# UNO-TH_Rev3e.net
KiCad netlist of a schematic drawn in EAGLE
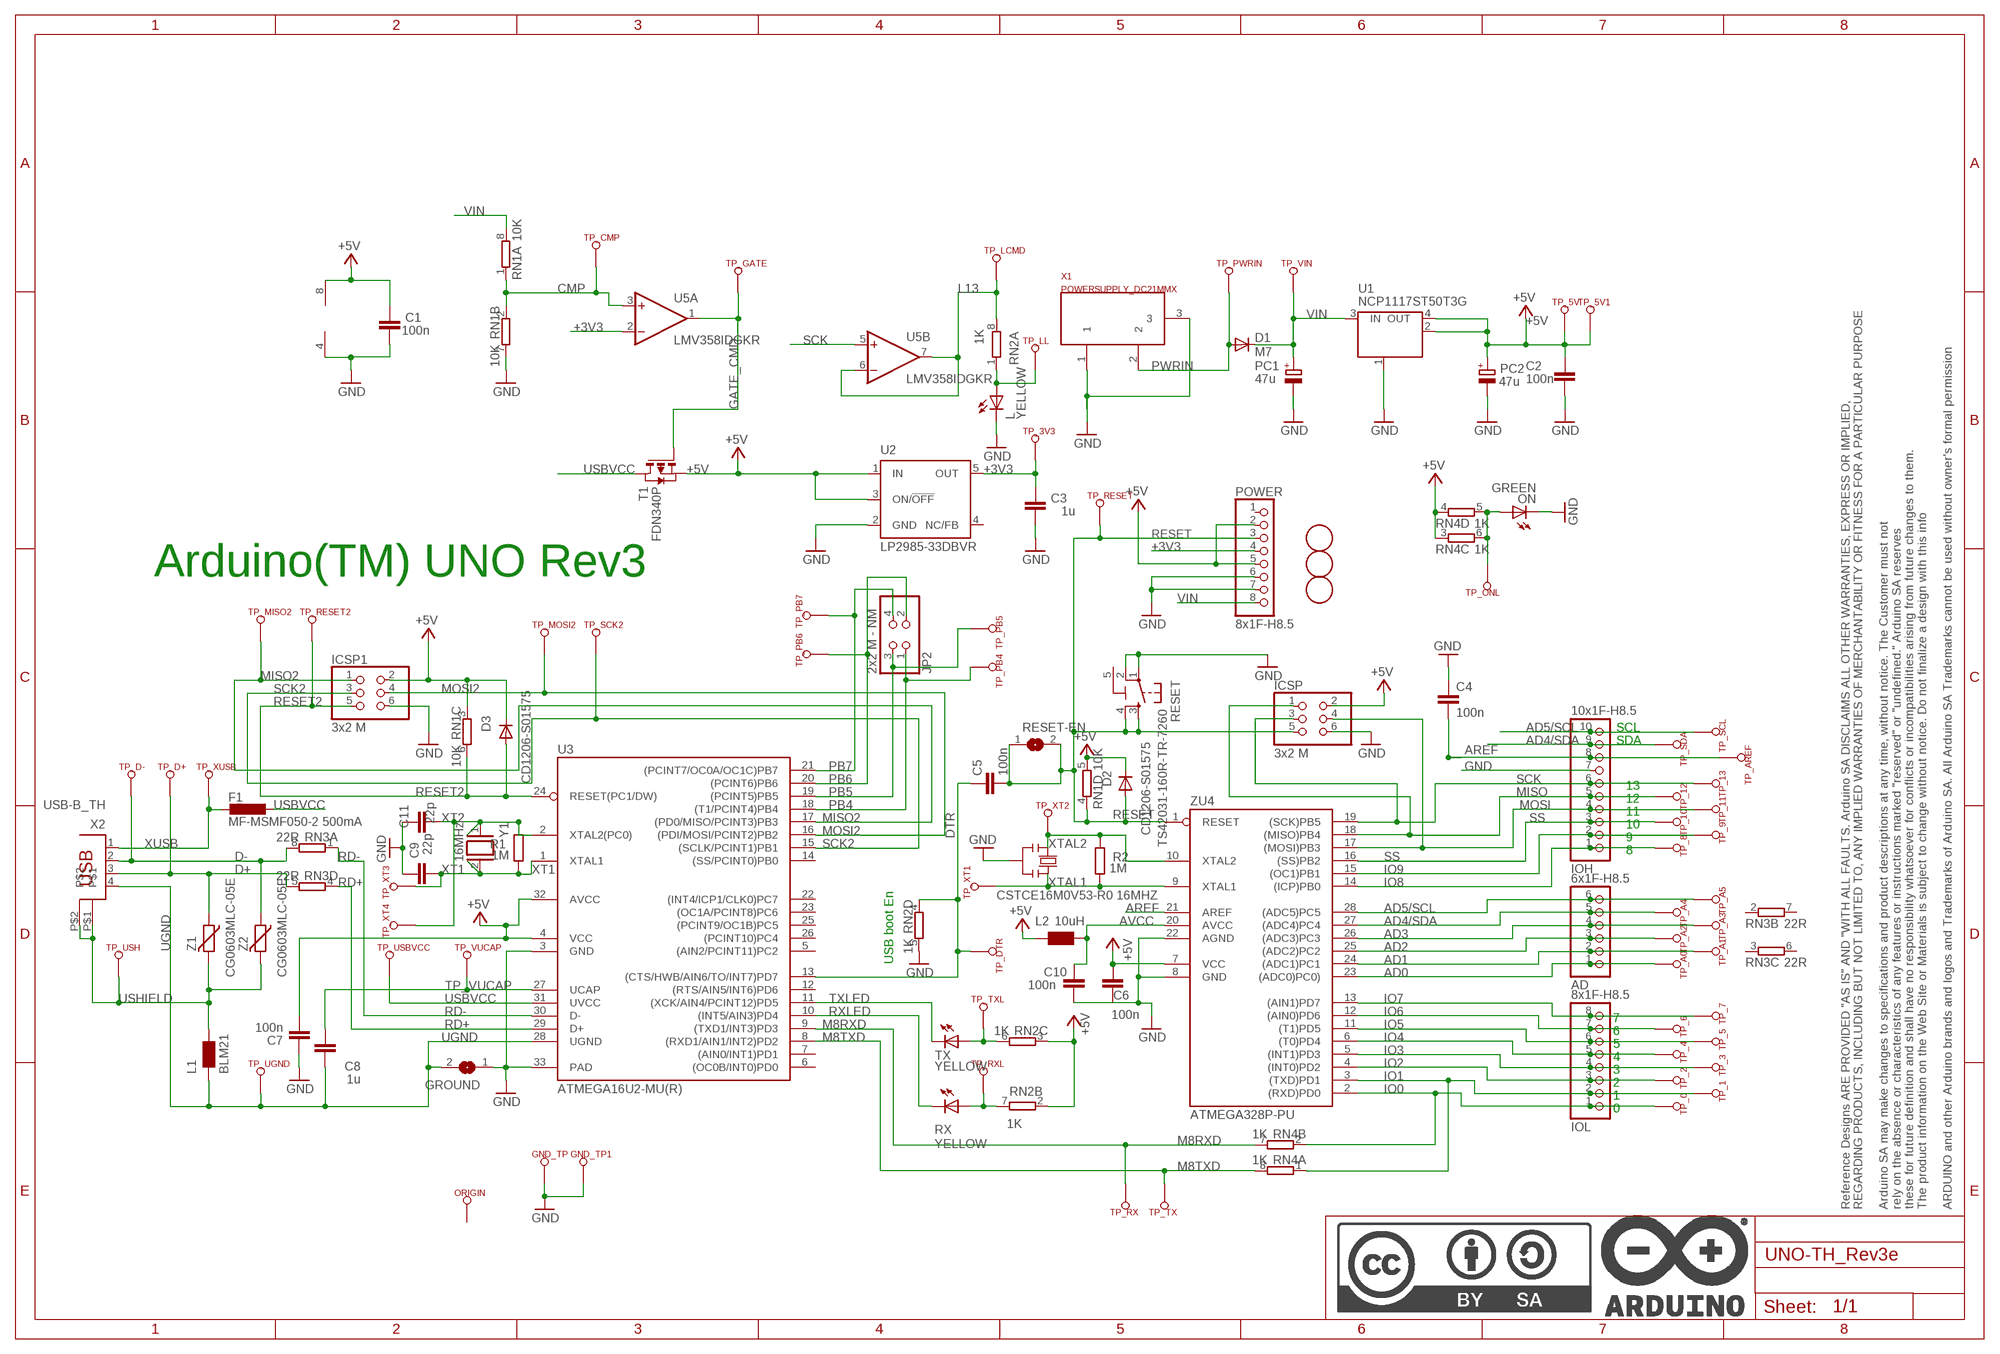
[diagram p0: schematic, sheet 1]

(export (version "E")
  (design (tool "Eeschema 10.0.6"))
  (components
    (comp (ref "AD")
      (value "6x1F-H8.5")
      (footprint "eagle-import:1X06")
      (libsource (lib "eagle-import") (part "PINHD-1X6"))
    )
    (comp (ref "C1")
      (value "100n")
      (footprint "eagle-import:C0603-ROUND")
      (libsource (lib "eagle-import") (part "C-EU0603-RND"))
    )
    (comp (ref "C2")
      (value "100n")
      (footprint "eagle-import:C0603-ROUND")
      (libsource (lib "eagle-import") (part "C-EU0603-RND"))
    )
    (comp (ref "C3")
      (value "1u")
      (footprint "eagle-import:C0603-ROUND")
      (libsource (lib "eagle-import") (part "C-EU0603-RND"))
    )
    (comp (ref "C4")
      (value "100n")
      (footprint "eagle-import:C0603-ROUND")
      (libsource (lib "eagle-import") (part "C-EU0603-RND"))
    )
    (comp (ref "C5")
      (value "100n")
      (footprint "eagle-import:C0603-ROUND")
      (libsource (lib "eagle-import") (part "C-EU0603-RND"))
    )
    (comp (ref "C6")
      (value "100n")
      (footprint "eagle-import:C0603-ROUND")
      (libsource (lib "eagle-import") (part "C-EU0603-RND"))
    )
    (comp (ref "C7")
      (value "100n")
      (footprint "eagle-import:C0603-ROUND")
      (libsource (lib "eagle-import") (part "C-EU0603-RND"))
    )
    (comp (ref "C8")
      (value "1u")
      (footprint "eagle-import:C0603-ROUND")
      (libsource (lib "eagle-import") (part "C-EU0603-RND"))
    )
    (comp (ref "C9")
      (value "22p")
      (footprint "eagle-import:C0603-ROUND")
      (libsource (lib "eagle-import") (part "C-EU0603-RND"))
    )
    (comp (ref "C10")
      (value "100n")
      (footprint "eagle-import:C0603-ROUND")
      (libsource (lib "eagle-import") (part "C-EU0603-RND"))
    )
    (comp (ref "C11")
      (value "22p")
      (footprint "eagle-import:C0603-ROUND")
      (libsource (lib "eagle-import") (part "C-EU0603-RND"))
    )
    (comp (ref "D1")
      (value "M7")
      (footprint "eagle-import:SMB")
      (libsource (lib "eagle-import") (part "DIODE-SMB"))
    )
    (comp (ref "D2")
      (value "CD1206-S01575")
      (footprint "eagle-import:MINIMELF")
      (libsource (lib "eagle-import") (part "DIODE-MINIMELF"))
    )
    (comp (ref "D3")
      (value "CD1206-S01575")
      (footprint "eagle-import:MINIMELF")
      (libsource (lib "eagle-import") (part "DIODE-MINIMELF"))
    )
    (comp (ref "F1")
      (value "MF-MSMF050-2 500mA")
      (footprint "eagle-import:L1812")
      (libsource (lib "eagle-import") (part "L-EUL1812"))
    )
    (comp (ref "FD1")
      (value "FIDUCIALMOUNT")
      (footprint "eagle-import:FIDUCIA-MOUNT")
      (libsource (lib "eagle-import") (part "FIDUCIALMOUNT"))
    )
    (comp (ref "FD2")
      (value "FIDUCIALMOUNT")
      (footprint "eagle-import:FIDUCIA-MOUNT")
      (libsource (lib "eagle-import") (part "FIDUCIALMOUNT"))
    )
    (comp (ref "FD3")
      (value "FIDUCIALMOUNT")
      (footprint "eagle-import:FIDUCIA-MOUNT")
      (libsource (lib "eagle-import") (part "FIDUCIALMOUNT"))
    )
    (comp (ref "FRAME1")
      (value "DNP")
      (footprint "eagle-import:FRAME")
      (libsource (lib "eagle-import") (part "A3-FRAME"))
    )
    (comp (ref "GND_TP")
      (value "TP_SP")
      (footprint "eagle-import:TP-SP")
      (libsource (lib "eagle-import") (part "TP_SP"))
    )
    (comp (ref "GND_TP1")
      (value "TP_SP")
      (footprint "eagle-import:TP-SP")
      (libsource (lib "eagle-import") (part "TP_SP"))
    )
    (comp (ref "GROUND")
      (value "SJ")
      (footprint "eagle-import:SJ")
      (libsource (lib "eagle-import") (part "SJ"))
    )
    (comp (ref "ICSP")
      (value "3x2 M")
      (footprint "eagle-import:2X03")
      (libsource (lib "eagle-import") (part "PINHD-2X3"))
    )
    (comp (ref "ICSP1")
      (value "3x2 M")
      (footprint "eagle-import:2X03")
      (libsource (lib "eagle-import") (part "PINHD-2X3"))
    )
    (comp (ref "IOH")
      (value "10x1F-H8.5")
      (footprint "eagle-import:1X10")
      (libsource (lib "eagle-import") (part "PINHD-1X10_ARD"))
    )
    (comp (ref "IOL")
      (value "8x1F-H8.5")
      (footprint "eagle-import:1X08")
      (libsource (lib "eagle-import") (part "PINHD-1X8"))
    )
    (comp (ref "JP2")
      (value "2x2 M - NM")
      (footprint "eagle-import:2X02")
      (libsource (lib "eagle-import") (part "PINHD-2X2"))
    )
    (comp (ref "L")
      (value "YELLOW")
      (footprint "eagle-import:CHIP-LED0805")
      (libsource (lib "eagle-import") (part "LEDCHIP-LED0805"))
    )
    (comp (ref "L1")
      (value "BLM21")
      (footprint "eagle-import:0805")
      (libsource (lib "eagle-import") (part "WE-CBF_0805"))
    )
    (comp (ref "L2")
      (value "10uH")
      (footprint "eagle-import:0805")
      (fields (field (name "PART_NUMBER") "CV201210-100K"))
      (libsource (lib "eagle-import") (part "0715_CV201210-100K"))
    )
    (comp (ref "ON")
      (value "GREEN")
      (footprint "eagle-import:CHIP-LED0805")
      (libsource (lib "eagle-import") (part "LEDCHIP-LED0805"))
    )
    (comp (ref "ORIGIN")
      (value "TP_SP")
      (footprint "eagle-import:TP-SP")
      (libsource (lib "eagle-import") (part "TP_SP"))
    )
    (comp (ref "PC1")
      (value "47u")
      (footprint "eagle-import:PANASONIC_D")
      (libsource (lib "eagle-import") (part "CPOL-EUD"))
    )
    (comp (ref "PC2")
      (value "47u")
      (footprint "eagle-import:PANASONIC_D")
      (libsource (lib "eagle-import") (part "CPOL-EUD"))
    )
    (comp (ref "POWER")
      (value "8x1F-H8.5")
      (footprint "eagle-import:1X08")
      (libsource (lib "eagle-import") (part "PINHD-1X8"))
    )
    (comp (ref "R1")
      (value "1M")
      (footprint "eagle-import:R0603-ROUND")
      (libsource (lib "eagle-import") (part "R-EU_R0603"))
    )
    (comp (ref "R2")
      (value "1M")
      (footprint "eagle-import:R0603-ROUND")
      (libsource (lib "eagle-import") (part "R-EU_R0603"))
    )
    (comp (ref "RESET")
      (value "TS42031-160R-TR-7260")
      (footprint "eagle-import:TS42")
      (libsource (lib "eagle-import") (part "TS42"))
    )
    (comp (ref "RESET-EN")
      (value "SJ")
      (footprint "eagle-import:SJ")
      (libsource (lib "eagle-import") (part "SJ"))
    )
    (comp (ref "RN1")
      (value "10K")
      (footprint "eagle-import:CAY16")
      (libsource (lib "eagle-import") (part "4R-NCAY16"))
    )
    (comp (ref "RN2")
      (value "1K")
      (footprint "eagle-import:CAY16")
      (libsource (lib "eagle-import") (part "4R-NCAY16"))
    )
    (comp (ref "RN3")
      (value "22R")
      (footprint "eagle-import:CAY16")
      (libsource (lib "eagle-import") (part "4R-NCAY16"))
    )
    (comp (ref "RN4")
      (value "1K")
      (footprint "eagle-import:CAY16")
      (libsource (lib "eagle-import") (part "4R-NCAY16"))
    )
    (comp (ref "RX")
      (value "YELLOW")
      (footprint "eagle-import:CHIP-LED0805")
      (libsource (lib "eagle-import") (part "LEDCHIP-LED0805"))
    )
    (comp (ref "T1")
      (value "FDN340P")
      (footprint "eagle-import:SOT-23")
      (libsource (lib "eagle-import") (part "PMOSSOT23"))
    )
    (comp (ref "TP_0")
      (value "TP_SP")
      (footprint "eagle-import:TP-SP")
      (libsource (lib "eagle-import") (part "TP_SP"))
    )
    (comp (ref "TP_1")
      (value "TP_SP")
      (footprint "eagle-import:TP-SP")
      (libsource (lib "eagle-import") (part "TP_SP"))
    )
    (comp (ref "TP_2")
      (value "TP_SP")
      (footprint "eagle-import:TP-SP")
      (libsource (lib "eagle-import") (part "TP_SP"))
    )
    (comp (ref "TP_3")
      (value "TP_SP")
      (footprint "eagle-import:TP-SP")
      (libsource (lib "eagle-import") (part "TP_SP"))
    )
    (comp (ref "TP_3V3")
      (value "TP_SP")
      (footprint "eagle-import:TP-SP")
      (libsource (lib "eagle-import") (part "TP_SP"))
    )
    (comp (ref "TP_4")
      (value "TP_SP")
      (footprint "eagle-import:TP-SP")
      (libsource (lib "eagle-import") (part "TP_SP"))
    )
    (comp (ref "TP_5")
      (value "TP_SP")
      (footprint "eagle-import:TP-SP")
      (libsource (lib "eagle-import") (part "TP_SP"))
    )
    (comp (ref "TP_5V")
      (value "TP_SP")
      (footprint "eagle-import:TP-SP")
      (libsource (lib "eagle-import") (part "TP_SP"))
    )
    (comp (ref "TP_5V1")
      (value "TP_SP")
      (footprint "eagle-import:TP-SP")
      (libsource (lib "eagle-import") (part "TP_SP"))
    )
    (comp (ref "TP_6")
      (value "TP_SP")
      (footprint "eagle-import:TP-SP")
      (libsource (lib "eagle-import") (part "TP_SP"))
    )
    (comp (ref "TP_7")
      (value "TP_SP")
      (footprint "eagle-import:TP-SP")
      (libsource (lib "eagle-import") (part "TP_SP"))
    )
    (comp (ref "TP_8")
      (value "TP_SP")
      (footprint "eagle-import:TP-SP")
      (libsource (lib "eagle-import") (part "TP_SP"))
    )
    (comp (ref "TP_9")
      (value "TP_SP")
      (footprint "eagle-import:TP-SP")
      (libsource (lib "eagle-import") (part "TP_SP"))
    )
    (comp (ref "TP_10")
      (value "TP_SP")
      (footprint "eagle-import:TP-SP")
      (libsource (lib "eagle-import") (part "TP_SP"))
    )
    (comp (ref "TP_11")
      (value "TP_SP")
      (footprint "eagle-import:TP-SP")
      (libsource (lib "eagle-import") (part "TP_SP"))
    )
    (comp (ref "TP_12")
      (value "TP_SP")
      (footprint "eagle-import:TP-SP")
      (libsource (lib "eagle-import") (part "TP_SP"))
    )
    (comp (ref "TP_13")
      (value "TP_SP")
      (footprint "eagle-import:TP-SP")
      (libsource (lib "eagle-import") (part "TP_SP"))
    )
    (comp (ref "TP_A0")
      (value "TP_SP")
      (footprint "eagle-import:TP-SP")
      (libsource (lib "eagle-import") (part "TP_SP"))
    )
    (comp (ref "TP_A1")
      (value "TP_SP")
      (footprint "eagle-import:TP-SP")
      (libsource (lib "eagle-import") (part "TP_SP"))
    )
    (comp (ref "TP_A2")
      (value "TP_SP")
      (footprint "eagle-import:TP-SP")
      (libsource (lib "eagle-import") (part "TP_SP"))
    )
    (comp (ref "TP_A3")
      (value "TP_SP")
      (footprint "eagle-import:TP-SP")
      (libsource (lib "eagle-import") (part "TP_SP"))
    )
    (comp (ref "TP_A4")
      (value "TP_SP")
      (footprint "eagle-import:TP-SP")
      (libsource (lib "eagle-import") (part "TP_SP"))
    )
    (comp (ref "TP_A5")
      (value "TP_SP")
      (footprint "eagle-import:TP-SP")
      (libsource (lib "eagle-import") (part "TP_SP"))
    )
    (comp (ref "TP_AREF")
      (value "TP_SP")
      (footprint "eagle-import:TP-SP")
      (libsource (lib "eagle-import") (part "TP_SP"))
    )
    (comp (ref "TP_CMP")
      (value "TP_SP")
      (footprint "eagle-import:TP-SP")
      (libsource (lib "eagle-import") (part "TP_SP"))
    )
    (comp (ref "TP_D+")
      (value "TP_SP")
      (footprint "eagle-import:TP-SP")
      (libsource (lib "eagle-import") (part "TP_SP"))
    )
    (comp (ref "TP_D-")
      (value "TP_SP")
      (footprint "eagle-import:TP-SP")
      (libsource (lib "eagle-import") (part "TP_SP"))
    )
    (comp (ref "TP_DTR")
      (value "TP_SP")
      (footprint "eagle-import:TP-SP")
      (libsource (lib "eagle-import") (part "TP_SP"))
    )
    (comp (ref "TP_GATE")
      (value "TP_SP")
      (footprint "eagle-import:TP-SP")
      (libsource (lib "eagle-import") (part "TP_SP"))
    )
    (comp (ref "TP_LCMD")
      (value "TP_SP")
      (footprint "eagle-import:TP-SP")
      (libsource (lib "eagle-import") (part "TP_SP"))
    )
    (comp (ref "TP_LL")
      (value "TP_SP")
      (footprint "eagle-import:TP-SP")
      (libsource (lib "eagle-import") (part "TP_SP"))
    )
    (comp (ref "TP_MISO2")
      (value "TP_SP")
      (footprint "eagle-import:TP-SP")
      (libsource (lib "eagle-import") (part "TP_SP"))
    )
    (comp (ref "TP_MOSI2")
      (value "TP_SP")
      (footprint "eagle-import:TP-SP")
      (libsource (lib "eagle-import") (part "TP_SP"))
    )
    (comp (ref "TP_ONL")
      (value "TP_SP")
      (footprint "eagle-import:TP-SP")
      (libsource (lib "eagle-import") (part "TP_SP"))
    )
    (comp (ref "TP_PB4")
      (value "TP_SP")
      (footprint "eagle-import:TP-SP")
      (libsource (lib "eagle-import") (part "TP_SP"))
    )
    (comp (ref "TP_PB5")
      (value "TP_SP")
      (footprint "eagle-import:TP-SP")
      (libsource (lib "eagle-import") (part "TP_SP"))
    )
    (comp (ref "TP_PB6")
      (value "TP_SP")
      (footprint "eagle-import:TP-SP")
      (libsource (lib "eagle-import") (part "TP_SP"))
    )
    (comp (ref "TP_PB7")
      (value "TP_SP")
      (footprint "eagle-import:TP-SP")
      (libsource (lib "eagle-import") (part "TP_SP"))
    )
    (comp (ref "TP_PWRIN")
      (value "TP_SP")
      (footprint "eagle-import:TP-SP")
      (libsource (lib "eagle-import") (part "TP_SP"))
    )
    (comp (ref "TP_RESET")
      (value "TP_SP")
      (footprint "eagle-import:TP-SP")
      (libsource (lib "eagle-import") (part "TP_SP"))
    )
    (comp (ref "TP_RESET2")
      (value "TP_SP")
      (footprint "eagle-import:TP-SP")
      (libsource (lib "eagle-import") (part "TP_SP"))
    )
    (comp (ref "TP_RX")
      (value "TP_SP")
      (footprint "eagle-import:TP-SP")
      (libsource (lib "eagle-import") (part "TP_SP"))
    )
    (comp (ref "TP_RXL")
      (value "TP_SP")
      (footprint "eagle-import:TP-SP")
      (libsource (lib "eagle-import") (part "TP_SP"))
    )
    (comp (ref "TP_SCK2")
      (value "TP_SP")
      (footprint "eagle-import:TP-SP")
      (libsource (lib "eagle-import") (part "TP_SP"))
    )
    (comp (ref "TP_SCL")
      (value "TP_SP")
      (footprint "eagle-import:TP-SP")
      (libsource (lib "eagle-import") (part "TP_SP"))
    )
    (comp (ref "TP_SDA")
      (value "TP_SP")
      (footprint "eagle-import:TP-SP")
      (libsource (lib "eagle-import") (part "TP_SP"))
    )
    (comp (ref "TP_TX")
      (value "TP_SP")
      (footprint "eagle-import:TP-SP")
      (libsource (lib "eagle-import") (part "TP_SP"))
    )
    (comp (ref "TP_TXL")
      (value "TP_SP")
      (footprint "eagle-import:TP-SP")
      (libsource (lib "eagle-import") (part "TP_SP"))
    )
    (comp (ref "TP_UGND")
      (value "TP_SP")
      (footprint "eagle-import:TP-SP")
      (libsource (lib "eagle-import") (part "TP_SP"))
    )
    (comp (ref "TP_USBVCC")
      (value "TP_SP")
      (footprint "eagle-import:TP-SP")
      (libsource (lib "eagle-import") (part "TP_SP"))
    )
    (comp (ref "TP_USH")
      (value "TP_SP")
      (footprint "eagle-import:TP-SP")
      (libsource (lib "eagle-import") (part "TP_SP"))
    )
    (comp (ref "TP_VIN")
      (value "TP_SP")
      (footprint "eagle-import:TP-SP")
      (libsource (lib "eagle-import") (part "TP_SP"))
    )
    (comp (ref "TP_VUCAP")
      (value "TP_SP")
      (footprint "eagle-import:TP-SP")
      (libsource (lib "eagle-import") (part "TP_SP"))
    )
    (comp (ref "TP_XT1")
      (value "TP_SP")
      (footprint "eagle-import:TP-SP")
      (libsource (lib "eagle-import") (part "TP_SP"))
    )
    (comp (ref "TP_XT2")
      (value "TP_SP")
      (footprint "eagle-import:TP-SP")
      (libsource (lib "eagle-import") (part "TP_SP"))
    )
    (comp (ref "TP_XT3")
      (value "TP_SP")
      (footprint "eagle-import:TP-SP")
      (libsource (lib "eagle-import") (part "TP_SP"))
    )
    (comp (ref "TP_XT4")
      (value "TP_SP")
      (footprint "eagle-import:TP-SP")
      (libsource (lib "eagle-import") (part "TP_SP"))
    )
    (comp (ref "TP_XUSB")
      (value "TP_SP")
      (footprint "eagle-import:TP-SP")
      (libsource (lib "eagle-import") (part "TP_SP"))
    )
    (comp (ref "TX")
      (value "YELLOW")
      (footprint "eagle-import:CHIP-LED0805")
      (libsource (lib "eagle-import") (part "LEDCHIP-LED0805"))
    )
    (comp (ref "U1")
      (value "NCP1117ST50T3G")
      (footprint "eagle-import:SOT223")
      (libsource (lib "eagle-import") (part "MC33269ST-3.3T3"))
    )
    (comp (ref "U2")
      (value "LP2985-33DBVR")
      (footprint "eagle-import:SOT23-DBV")
      (libsource (lib "eagle-import") (part "LP2985-XXDBVR33"))
    )
    (comp (ref "U3")
      (value "ATMEGA16U2-MU(R)")
      (footprint "eagle-import:MLF32")
      (libsource (lib "eagle-import") (part "ATMEGA16U2-MU"))
    )
    (comp (ref "U5")
      (value "LMV358IDGKR")
      (footprint "eagle-import:MSOP08")
      (libsource (lib "eagle-import") (part "LMV358?MMX"))
    )
    (comp (ref "X1")
      (value "POWERSUPPLY_DC21MMX")
      (footprint "eagle-import:POWERSUPPLY_DC-21MM")
      (libsource (lib "eagle-import") (part "POWERSUPPLY_DC21MMX"))
    )
    (comp (ref "X2")
      (value "USB-B_TH")
      (footprint "eagle-import:PN61729")
      (libsource (lib "eagle-import") (part "PN61729"))
    )
    (comp (ref "Y1")
      (value "16MHz")
      (footprint "eagle-import:QS")
      (libsource (lib "eagle-import") (part "XTAL/S"))
    )
    (comp (ref "Y2")
      (value "CSTCE16M0V53-R0 16MHZ")
      (footprint "eagle-import:RESONATOR")
      (libsource (lib "eagle-import") (part "RESONATORMU"))
    )
    (comp (ref "Z1")
      (value "CG0603MLC-05E")
      (footprint "eagle-import:CT_CN0603")
      (libsource (lib "eagle-import") (part "VARISTORCN0603"))
    )
    (comp (ref "Z2")
      (value "CG0603MLC-05E")
      (footprint "eagle-import:CT_CN0603")
      (libsource (lib "eagle-import") (part "VARISTORCN0603"))
    )
    (comp (ref "ZU4")
      (value "ATMEGA328P-PU")
      (footprint "eagle-import:DIL28-3")
      (libsource (lib "eagle-import") (part "ATMEGA328P-PU"))
    )
  )
  (nets
    (net (code "1") (name "+5V") (class "Default")
      (node (ref "C1") (pin "2") (pinfunction "2_2") (pintype "passive"))
      (node (ref "C2") (pin "2") (pinfunction "2_2") (pintype "passive"))
      (node (ref "C6") (pin "2") (pinfunction "2_2") (pintype "passive"))
      (node (ref "C7") (pin "1") (pinfunction "1_1") (pintype "passive"))
      (node (ref "D2") (pin "C") (pinfunction "C_C") (pintype "passive"))
      (node (ref "D3") (pin "C") (pinfunction "C_C") (pintype "passive"))
      (node (ref "ICSP") (pin "2") (pinfunction "2_2") (pintype "passive"))
      (node (ref "ICSP1") (pin "2") (pinfunction "2_2") (pintype "passive"))
      (node (ref "L2") (pin "1") (pinfunction "1_1") (pintype "passive"))
      (node (ref "PC2") (pin "+") (pinfunction "+_+") (pintype "passive"))
      (node (ref "POWER") (pin "2") (pinfunction "2_2") (pintype "passive"))
      (node (ref "POWER") (pin "5") (pinfunction "5_5") (pintype "passive"))
      (node (ref "RN1") (pin "3") (pinfunction "1_3") (pintype "passive"))
      (node (ref "RN1") (pin "5") (pinfunction "2_5") (pintype "passive"))
      (node (ref "RN2") (pin "2") (pinfunction "1_2") (pintype "passive"))
      (node (ref "RN2") (pin "3") (pinfunction "1_3") (pintype "passive"))
      (node (ref "RN4") (pin "3") (pinfunction "1_3") (pintype "passive"))
      (node (ref "RN4") (pin "4") (pinfunction "1_4") (pintype "passive"))
      (node (ref "T1") (pin "2") (pinfunction "S_2") (pintype "passive"))
      (node (ref "TP_5V") (pin "X") (pinfunction "TESTP_X") (pintype "passive"))
      (node (ref "TP_5V1") (pin "X") (pinfunction "TESTP_X") (pintype "passive"))
      (node (ref "U1") (pin "2") (pinfunction "OUT_2") (pintype "passive"))
      (node (ref "U1") (pin "4") (pinfunction "OUT_4") (pintype "passive"))
      (node (ref "U2") (pin "1") (pinfunction "IN_1") (pintype "input"))
      (node (ref "U2") (pin "3") (pinfunction "ON/~{OFF}_3") (pintype "input"))
      (node (ref "U3") (pin "32") (pinfunction "AVCC_32") (pintype "power_in"))
      (node (ref "U3") (pin "4") (pinfunction "VCC_4") (pintype "power_in"))
      (node (ref "U5") (pin "8") (pinfunction "V+_8") (pintype "power_in"))
      (node (ref "ZU4") (pin "7") (pinfunction "VCC_7") (pintype "power_in"))
    )
    (net (code "2") (name "/+3V3") (class "Default")
      (node (ref "C3") (pin "2") (pinfunction "2_2") (pintype "passive"))
      (node (ref "POWER") (pin "4") (pinfunction "4_4") (pintype "passive"))
      (node (ref "TP_3V3") (pin "X") (pinfunction "TESTP_X") (pintype "passive"))
      (node (ref "U2") (pin "5") (pinfunction "OUT_5") (pintype "passive"))
      (node (ref "U5") (pin "2") (pinfunction "-IN_2") (pintype "input"))
    )
    (net (code "3") (name "/5-GND") (class "Default")
      (node (ref "RESET") (pin "5") (pinfunction "5-GND_5") (pintype "power_in"))
    )
    (net (code "4") (name "/AD0") (class "Default")
      (node (ref "AD") (pin "1") (pinfunction "1_1") (pintype "passive"))
      (node (ref "TP_A0") (pin "X") (pinfunction "TESTP_X") (pintype "passive"))
      (node (ref "ZU4") (pin "23") (pinfunction "(ADC0)PC0)_23") (pintype "bidirectional"))
    )
    (net (code "5") (name "/AD1") (class "Default")
      (node (ref "AD") (pin "2") (pinfunction "2_2") (pintype "passive"))
      (node (ref "TP_A1") (pin "X") (pinfunction "TESTP_X") (pintype "passive"))
      (node (ref "ZU4") (pin "24") (pinfunction "(ADC1)PC1_24") (pintype "bidirectional"))
    )
    (net (code "6") (name "/AD2") (class "Default")
      (node (ref "AD") (pin "3") (pinfunction "3_3") (pintype "passive"))
      (node (ref "TP_A2") (pin "X") (pinfunction "TESTP_X") (pintype "passive"))
      (node (ref "ZU4") (pin "25") (pinfunction "(ADC2)PC2_25") (pintype "bidirectional"))
    )
    (net (code "7") (name "/AD3") (class "Default")
      (node (ref "AD") (pin "4") (pinfunction "4_4") (pintype "passive"))
      (node (ref "TP_A3") (pin "X") (pinfunction "TESTP_X") (pintype "passive"))
      (node (ref "ZU4") (pin "26") (pinfunction "(ADC3)PC3_26") (pintype "bidirectional"))
    )
    (net (code "8") (name "/AD4{slash}SDA") (class "Default")
      (node (ref "AD") (pin "5") (pinfunction "5_5") (pintype "passive"))
      (node (ref "IOH") (pin "9") (pinfunction "9_9") (pintype "passive"))
      (node (ref "TP_A4") (pin "X") (pinfunction "TESTP_X") (pintype "passive"))
      (node (ref "TP_SDA") (pin "X") (pinfunction "TESTP_X") (pintype "passive"))
      (node (ref "ZU4") (pin "27") (pinfunction "(ADC4)PC4_27") (pintype "bidirectional"))
    )
    (net (code "9") (name "/AD5{slash}SCL") (class "Default")
      (node (ref "AD") (pin "6") (pinfunction "6_6") (pintype "passive"))
      (node (ref "IOH") (pin "10") (pinfunction "10_10") (pintype "passive"))
      (node (ref "TP_A5") (pin "X") (pinfunction "TESTP_X") (pintype "passive"))
      (node (ref "TP_SCL") (pin "X") (pinfunction "TESTP_X") (pintype "passive"))
      (node (ref "ZU4") (pin "28") (pinfunction "(ADC5)PC5_28") (pintype "bidirectional"))
    )
    (net (code "10") (name "/AREF") (class "Default")
      (node (ref "C4") (pin "2") (pinfunction "2_2") (pintype "passive"))
      (node (ref "IOH") (pin "8") (pinfunction "8_8") (pintype "passive"))
      (node (ref "TP_AREF") (pin "X") (pinfunction "TESTP_X") (pintype "passive"))
      (node (ref "ZU4") (pin "21") (pinfunction "AREF_21") (pintype "passive"))
    )
    (net (code "11") (name "/AVCC") (class "Default")
      (node (ref "C10") (pin "2") (pinfunction "2_2") (pintype "passive"))
      (node (ref "L2") (pin "2") (pinfunction "2_2") (pintype "passive"))
      (node (ref "ZU4") (pin "20") (pinfunction "AVCC_20") (pintype "power_in"))
    )
    (net (code "12") (name "/CMP") (class "Default")
      (node (ref "RN1") (pin "1") (pinfunction "1_1") (pintype "passive"))
      (node (ref "RN1") (pin "2") (pinfunction "1_2") (pintype "passive"))
      (node (ref "TP_CMP") (pin "X") (pinfunction "TESTP_X") (pintype "passive"))
      (node (ref "U5") (pin "3") (pinfunction "+IN_3") (pintype "input"))
    )
    (net (code "13") (name "/D+") (class "Default")
      (node (ref "RN3") (pin "5") (pinfunction "2_5") (pintype "passive"))
      (node (ref "TP_D+") (pin "X") (pinfunction "TESTP_X") (pintype "passive"))
      (node (ref "X2") (pin "3") (pinfunction "3_3") (pintype "bidirectional"))
      (node (ref "Z1") (pin "1") (pinfunction "1_1") (pintype "passive"))
    )
    (net (code "14") (name "/D-") (class "Default")
      (node (ref "RN3") (pin "8") (pinfunction "2_8") (pintype "passive"))
      (node (ref "TP_D-") (pin "X") (pinfunction "TESTP_X") (pintype "passive"))
      (node (ref "X2") (pin "2") (pinfunction "2_2") (pintype "bidirectional"))
      (node (ref "Z2") (pin "1") (pinfunction "1_1") (pintype "passive"))
    )
    (net (code "15") (name "/DTR") (class "Default")
      (node (ref "C5") (pin "1") (pinfunction "1_1") (pintype "passive"))
      (node (ref "RN2") (pin "4") (pinfunction "1_4") (pintype "passive"))
      (node (ref "TP_DTR") (pin "X") (pinfunction "TESTP_X") (pintype "passive"))
      (node (ref "U3") (pin "13") (pinfunction "(CTS/HWB/AIN6/TO/INT7)PD7_13") (pintype "bidirectional"))
    )
    (net (code "16") (name "/GATE_CMD") (class "Default")
      (node (ref "T1") (pin "3") (pinfunction "G_3") (pintype "passive"))
      (node (ref "TP_GATE") (pin "X") (pinfunction "TESTP_X") (pintype "passive"))
      (node (ref "U5") (pin "1") (pinfunction "OUT_1") (pintype "output"))
    )
    (net (code "17") (name "/IO0") (class "Default")
      (node (ref "IOL") (pin "1") (pinfunction "1_1") (pintype "passive"))
      (node (ref "RN4") (pin "2") (pinfunction "1_2") (pintype "passive"))
      (node (ref "TP_0") (pin "X") (pinfunction "TESTP_X") (pintype "passive"))
      (node (ref "ZU4") (pin "2") (pinfunction "(RXD)PD0_2") (pintype "bidirectional"))
    )
    (net (code "18") (name "/IO1") (class "Default")
      (node (ref "IOL") (pin "2") (pinfunction "2_2") (pintype "passive"))
      (node (ref "RN4") (pin "1") (pinfunction "1_1") (pintype "passive"))
      (node (ref "TP_1") (pin "X") (pinfunction "TESTP_X") (pintype "passive"))
      (node (ref "ZU4") (pin "3") (pinfunction "(TXD)PD1_3") (pintype "bidirectional"))
    )
    (net (code "19") (name "/IO2") (class "Default")
      (node (ref "IOL") (pin "3") (pinfunction "3_3") (pintype "passive"))
      (node (ref "TP_2") (pin "X") (pinfunction "TESTP_X") (pintype "passive"))
      (node (ref "ZU4") (pin "4") (pinfunction "(INT0)PD2_4") (pintype "bidirectional"))
    )
    (net (code "20") (name "/IO3") (class "Default")
      (node (ref "IOL") (pin "4") (pinfunction "4_4") (pintype "passive"))
      (node (ref "TP_3") (pin "X") (pinfunction "TESTP_X") (pintype "passive"))
      (node (ref "ZU4") (pin "5") (pinfunction "(INT1)PD3_5") (pintype "bidirectional"))
    )
    (net (code "21") (name "/IO4") (class "Default")
      (node (ref "IOL") (pin "5") (pinfunction "5_5") (pintype "passive"))
      (node (ref "TP_4") (pin "X") (pinfunction "TESTP_X") (pintype "passive"))
      (node (ref "ZU4") (pin "6") (pinfunction "(T0)PD4_6") (pintype "bidirectional"))
    )
    (net (code "22") (name "/IO5") (class "Default")
      (node (ref "IOL") (pin "6") (pinfunction "6_6") (pintype "passive"))
      (node (ref "TP_5") (pin "X") (pinfunction "TESTP_X") (pintype "passive"))
      (node (ref "ZU4") (pin "11") (pinfunction "(T1)PD5_11") (pintype "bidirectional"))
    )
    (net (code "23") (name "/IO6") (class "Default")
      (node (ref "IOL") (pin "7") (pinfunction "7_7") (pintype "passive"))
      (node (ref "TP_6") (pin "X") (pinfunction "TESTP_X") (pintype "passive"))
      (node (ref "ZU4") (pin "12") (pinfunction "(AIN0)PD6_12") (pintype "bidirectional"))
    )
    (net (code "24") (name "/IO7") (class "Default")
      (node (ref "IOL") (pin "8") (pinfunction "8_8") (pintype "passive"))
      (node (ref "TP_7") (pin "X") (pinfunction "TESTP_X") (pintype "passive"))
      (node (ref "ZU4") (pin "13") (pinfunction "(AIN1)PD7_13") (pintype "bidirectional"))
    )
    (net (code "25") (name "/IO8") (class "Default")
      (node (ref "IOH") (pin "1") (pinfunction "1_1") (pintype "passive"))
      (node (ref "TP_8") (pin "X") (pinfunction "TESTP_X") (pintype "passive"))
      (node (ref "ZU4") (pin "14") (pinfunction "(ICP)PB0_14") (pintype "bidirectional"))
    )
    (net (code "26") (name "/IO9") (class "Default")
      (node (ref "IOH") (pin "2") (pinfunction "2_2") (pintype "passive"))
      (node (ref "TP_9") (pin "X") (pinfunction "TESTP_X") (pintype "passive"))
      (node (ref "ZU4") (pin "15") (pinfunction "(OC1)PB1_15") (pintype "bidirectional"))
    )
    (net (code "27") (name "/L13") (class "Default")
      (node (ref "RN2") (pin "8") (pinfunction "2_8") (pintype "passive"))
      (node (ref "TP_LCMD") (pin "X") (pinfunction "TESTP_X") (pintype "passive"))
      (node (ref "U5") (pin "6") (pinfunction "-IN_6") (pintype "input"))
      (node (ref "U5") (pin "7") (pinfunction "OUT_7") (pintype "output"))
    )
    (net (code "28") (name "/M8RXD") (class "Default")
      (node (ref "RN4") (pin "7") (pinfunction "2_7") (pintype "passive"))
      (node (ref "TP_RX") (pin "X") (pinfunction "TESTP_X") (pintype "passive"))
      (node (ref "U3") (pin "9") (pinfunction "(TXD1/INT3)PD3_9") (pintype "bidirectional"))
    )
    (net (code "29") (name "/M8TXD") (class "Default")
      (node (ref "RN4") (pin "8") (pinfunction "2_8") (pintype "passive"))
      (node (ref "TP_TX") (pin "X") (pinfunction "TESTP_X") (pintype "passive"))
      (node (ref "U3") (pin "8") (pinfunction "(RXD1/AIN1/INT2)PD2_8") (pintype "bidirectional"))
    )
    (net (code "30") (name "/MISO") (class "Default")
      (node (ref "ICSP") (pin "1") (pinfunction "1_1") (pintype "passive"))
      (node (ref "IOH") (pin "5") (pinfunction "5_5") (pintype "passive"))
      (node (ref "TP_12") (pin "X") (pinfunction "TESTP_X") (pintype "passive"))
      (node (ref "ZU4") (pin "18") (pinfunction "(MISO)PB4_18") (pintype "bidirectional"))
    )
    (net (code "31") (name "/MISO2") (class "Default")
      (node (ref "ICSP1") (pin "1") (pinfunction "1_1") (pintype "passive"))
      (node (ref "TP_MISO2") (pin "X") (pinfunction "TESTP_X") (pintype "passive"))
      (node (ref "U3") (pin "17") (pinfunction "(PD0/MISO/PCINT3)PB3_17") (pintype "bidirectional"))
    )
    (net (code "32") (name "/MOSI") (class "Default")
      (node (ref "ICSP") (pin "4") (pinfunction "4_4") (pintype "passive"))
      (node (ref "IOH") (pin "4") (pinfunction "4_4") (pintype "passive"))
      (node (ref "TP_11") (pin "X") (pinfunction "TESTP_X") (pintype "passive"))
      (node (ref "ZU4") (pin "17") (pinfunction "(MOSI)PB3_17") (pintype "bidirectional"))
    )
    (net (code "33") (name "/MOSI2") (class "Default")
      (node (ref "ICSP1") (pin "4") (pinfunction "4_4") (pintype "passive"))
      (node (ref "TP_MOSI2") (pin "X") (pinfunction "TESTP_X") (pintype "passive"))
      (node (ref "U3") (pin "16") (pinfunction "(PDI/MOSI/PCINT2)PB2_16") (pintype "bidirectional"))
    )
    (net (code "34") (name "/PB4") (class "Default")
      (node (ref "JP2") (pin "1") (pinfunction "1_1") (pintype "passive"))
      (node (ref "TP_PB4") (pin "X") (pinfunction "TESTP_X") (pintype "passive"))
      (node (ref "U3") (pin "18") (pinfunction "(T1/PCINT4)PB4_18") (pintype "bidirectional"))
    )
    (net (code "35") (name "/PB5") (class "Default")
      (node (ref "JP2") (pin "3") (pinfunction "3_3") (pintype "passive"))
      (node (ref "TP_PB5") (pin "X") (pinfunction "TESTP_X") (pintype "passive"))
      (node (ref "U3") (pin "19") (pinfunction "(PCINT5)PB5_19") (pintype "bidirectional"))
    )
    (net (code "36") (name "/PB6") (class "Default")
      (node (ref "JP2") (pin "2") (pinfunction "2_2") (pintype "passive"))
      (node (ref "TP_PB6") (pin "X") (pinfunction "TESTP_X") (pintype "passive"))
      (node (ref "U3") (pin "20") (pinfunction "(PCINT6)PB6_20") (pintype "bidirectional"))
    )
    (net (code "37") (name "/PB7") (class "Default")
      (node (ref "JP2") (pin "4") (pinfunction "4_4") (pintype "passive"))
      (node (ref "TP_PB7") (pin "X") (pinfunction "TESTP_X") (pintype "passive"))
      (node (ref "U3") (pin "21") (pinfunction "(PCINT7/OC0A/OC1C)PB7_21") (pintype "bidirectional"))
    )
    (net (code "38") (name "/PWRIN") (class "Default")
      (node (ref "D1") (pin "A") (pinfunction "A_A") (pintype "passive"))
      (node (ref "TP_PWRIN") (pin "X") (pinfunction "TESTP_X") (pintype "passive"))
      (node (ref "X1") (pin "2") (pinfunction "2_2") (pintype "power_in"))
    )
    (net (code "39") (name "/RD+") (class "Default")
      (node (ref "RN3") (pin "4") (pinfunction "1_4") (pintype "passive"))
      (node (ref "U3") (pin "29") (pinfunction "D+_29") (pintype "bidirectional"))
    )
    (net (code "40") (name "/RD-") (class "Default")
      (node (ref "RN3") (pin "1") (pinfunction "1_1") (pintype "passive"))
      (node (ref "U3") (pin "30") (pinfunction "D-_30") (pintype "bidirectional"))
    )
    (net (code "41") (name "/RESET") (class "Default")
      (node (ref "C5") (pin "2") (pinfunction "2_2") (pintype "passive"))
      (node (ref "D2") (pin "A") (pinfunction "A_A") (pintype "passive"))
      (node (ref "ICSP") (pin "5") (pinfunction "5_5") (pintype "passive"))
      (node (ref "POWER") (pin "3") (pinfunction "3_3") (pintype "passive"))
      (node (ref "RESET") (pin "3") (pinfunction "3_3") (pintype "passive"))
      (node (ref "RESET") (pin "4") (pinfunction "4_4") (pintype "passive"))
      (node (ref "RESET-EN") (pin "1") (pinfunction "1_1") (pintype "passive"))
      (node (ref "RESET-EN") (pin "2") (pinfunction "2_2") (pintype "passive"))
      (node (ref "RN1") (pin "4") (pinfunction "1_4") (pintype "passive"))
      (node (ref "TP_RESET") (pin "X") (pinfunction "TESTP_X") (pintype "passive"))
      (node (ref "ZU4") (pin "1") (pinfunction "RESET_1") (pintype "input"))
    )
    (net (code "42") (name "/RESET2") (class "Default")
      (node (ref "D3") (pin "A") (pinfunction "A_A") (pintype "passive"))
      (node (ref "ICSP1") (pin "5") (pinfunction "5_5") (pintype "passive"))
      (node (ref "RN1") (pin "6") (pinfunction "2_6") (pintype "passive"))
      (node (ref "TP_RESET2") (pin "X") (pinfunction "TESTP_X") (pintype "passive"))
      (node (ref "U3") (pin "24") (pinfunction "RESET(PC1/DW)_24") (pintype "input"))
    )
    (net (code "43") (name "/RXLED") (class "Default")
      (node (ref "RX") (pin "C") (pinfunction "C_C") (pintype "passive"))
      (node (ref "U3") (pin "10") (pinfunction "(INT5/AIN3)PD4_10") (pintype "bidirectional"))
    )
    (net (code "44") (name "/SCK") (class "Default")
      (node (ref "ICSP") (pin "3") (pinfunction "3_3") (pintype "passive"))
      (node (ref "IOH") (pin "6") (pinfunction "6_6") (pintype "passive"))
      (node (ref "TP_13") (pin "X") (pinfunction "TESTP_X") (pintype "passive"))
      (node (ref "U5") (pin "5") (pinfunction "+IN_5") (pintype "input"))
      (node (ref "ZU4") (pin "19") (pinfunction "(SCK)PB5_19") (pintype "bidirectional"))
    )
    (net (code "45") (name "/SCK2") (class "Default")
      (node (ref "ICSP1") (pin "3") (pinfunction "3_3") (pintype "passive"))
      (node (ref "TP_SCK2") (pin "X") (pinfunction "TESTP_X") (pintype "passive"))
      (node (ref "U3") (pin "15") (pinfunction "(SCLK/PCINT1)PB1_15") (pintype "bidirectional"))
    )
    (net (code "46") (name "/SS") (class "Default")
      (node (ref "IOH") (pin "3") (pinfunction "3_3") (pintype "passive"))
      (node (ref "TP_10") (pin "X") (pinfunction "TESTP_X") (pintype "passive"))
      (node (ref "ZU4") (pin "16") (pinfunction "(SS)PB2_16") (pintype "bidirectional"))
    )
    (net (code "47") (name "/TP_VUCAP") (class "Default")
      (node (ref "C8") (pin "1") (pinfunction "1_1") (pintype "passive"))
      (node (ref "TP_VUCAP") (pin "X") (pinfunction "TESTP_X") (pintype "passive"))
      (node (ref "U3") (pin "27") (pinfunction "UCAP_27") (pintype "passive"))
    )
    (net (code "48") (name "/TXLED") (class "Default")
      (node (ref "TX") (pin "C") (pinfunction "C_C") (pintype "passive"))
      (node (ref "U3") (pin "11") (pinfunction "(XCK/AIN4/PCINT12)PD5_11") (pintype "bidirectional"))
    )
    (net (code "49") (name "/UGND") (class "Default")
      (node (ref "C8") (pin "2") (pinfunction "2_2") (pintype "passive"))
      (node (ref "GROUND") (pin "2") (pinfunction "2_2") (pintype "passive"))
      (node (ref "L1") (pin "1") (pinfunction "1_1") (pintype "passive"))
      (node (ref "TP_UGND") (pin "X") (pinfunction "TESTP_X") (pintype "passive"))
      (node (ref "U3") (pin "28") (pinfunction "UGND_28") (pintype "power_in"))
      (node (ref "X2") (pin "4") (pinfunction "4_4") (pintype "bidirectional"))
    )
    (net (code "50") (name "/USBVCC") (class "Default")
      (node (ref "F1") (pin "1") (pinfunction "1_1") (pintype "passive"))
      (node (ref "T1") (pin "1") (pinfunction "D_1") (pintype "passive"))
      (node (ref "TP_USBVCC") (pin "X") (pinfunction "TESTP_X") (pintype "passive"))
      (node (ref "U3") (pin "31") (pinfunction "UVCC_31") (pintype "power_in"))
    )
    (net (code "51") (name "/USHIELD") (class "Default")
      (node (ref "L1") (pin "2") (pinfunction "2_2") (pintype "passive"))
      (node (ref "TP_USH") (pin "X") (pinfunction "TESTP_X") (pintype "passive"))
      (node (ref "X2") (pin "P$1") (pinfunction "P$1_P$1") (pintype "bidirectional"))
      (node (ref "X2") (pin "P$2") (pinfunction "P$2_P$2") (pintype "bidirectional"))
      (node (ref "Z1") (pin "2") (pinfunction "2_2") (pintype "passive"))
      (node (ref "Z2") (pin "2") (pinfunction "2_2") (pintype "passive"))
    )
    (net (code "52") (name "/VIN") (class "Default")
      (node (ref "D1") (pin "C") (pinfunction "C_C") (pintype "passive"))
      (node (ref "PC1") (pin "+") (pinfunction "+_+") (pintype "passive"))
      (node (ref "POWER") (pin "8") (pinfunction "8_8") (pintype "passive"))
      (node (ref "RN1") (pin "8") (pinfunction "2_8") (pintype "passive"))
      (node (ref "TP_VIN") (pin "X") (pinfunction "TESTP_X") (pintype "passive"))
      (node (ref "U1") (pin "3") (pinfunction "IN_3") (pintype "input"))
    )
    (net (code "53") (name "/XT1") (class "Default")
      (node (ref "C9") (pin "1") (pinfunction "1_1") (pintype "passive"))
      (node (ref "R1") (pin "1") (pinfunction "1_1") (pintype "passive"))
      (node (ref "TP_XT3") (pin "X") (pinfunction "TESTP_X") (pintype "passive"))
      (node (ref "U3") (pin "1") (pinfunction "XTAL1_1") (pintype "bidirectional"))
      (node (ref "Y1") (pin "2") (pinfunction "2_2") (pintype "passive"))
    )
    (net (code "54") (name "/XT2") (class "Default")
      (node (ref "C11") (pin "1") (pinfunction "1_1") (pintype "passive"))
      (node (ref "R1") (pin "2") (pinfunction "2_2") (pintype "passive"))
      (node (ref "TP_XT4") (pin "X") (pinfunction "TESTP_X") (pintype "passive"))
      (node (ref "U3") (pin "2") (pinfunction "XTAL2(PC0)_2") (pintype "bidirectional"))
      (node (ref "Y1") (pin "1") (pinfunction "1_1") (pintype "passive"))
    )
    (net (code "55") (name "/XTAL1") (class "Default")
      (node (ref "R2") (pin "1") (pinfunction "1_1") (pintype "passive"))
      (node (ref "TP_XT1") (pin "X") (pinfunction "TESTP_X") (pintype "passive"))
      (node (ref "Y2") (pin "3") (pinfunction "3_3") (pintype "passive"))
      (node (ref "ZU4") (pin "9") (pinfunction "XTAL1_9") (pintype "bidirectional"))
    )
    (net (code "56") (name "/XTAL2") (class "Default")
      (node (ref "R2") (pin "2") (pinfunction "2_2") (pintype "passive"))
      (node (ref "TP_XT2") (pin "X") (pinfunction "TESTP_X") (pintype "passive"))
      (node (ref "Y2") (pin "1") (pinfunction "1_1") (pintype "passive"))
      (node (ref "ZU4") (pin "10") (pinfunction "XTAL2_10") (pintype "bidirectional"))
    )
    (net (code "57") (name "/XUSB") (class "Default")
      (node (ref "F1") (pin "2") (pinfunction "2_2") (pintype "passive"))
      (node (ref "TP_XUSB") (pin "X") (pinfunction "TESTP_X") (pintype "passive"))
      (node (ref "X2") (pin "1") (pinfunction "1_1") (pintype "bidirectional"))
    )
    (net (code "58") (name "GND") (class "Default")
      (node (ref "C1") (pin "1") (pinfunction "1_1") (pintype "passive"))
      (node (ref "C10") (pin "1") (pinfunction "1_1") (pintype "passive"))
      (node (ref "C11") (pin "2") (pinfunction "2_2") (pintype "passive"))
      (node (ref "C2") (pin "1") (pinfunction "1_1") (pintype "passive"))
      (node (ref "C3") (pin "1") (pinfunction "1_1") (pintype "passive"))
      (node (ref "C4") (pin "1") (pinfunction "1_1") (pintype "passive"))
      (node (ref "C6") (pin "1") (pinfunction "1_1") (pintype "passive"))
      (node (ref "C7") (pin "2") (pinfunction "2_2") (pintype "passive"))
      (node (ref "C9") (pin "2") (pinfunction "2_2") (pintype "passive"))
      (node (ref "GND_TP") (pin "X") (pinfunction "TESTP_X") (pintype "passive"))
      (node (ref "GND_TP1") (pin "X") (pinfunction "TESTP_X") (pintype "passive"))
      (node (ref "GROUND") (pin "1") (pinfunction "1_1") (pintype "passive"))
      (node (ref "ICSP") (pin "6") (pinfunction "6_6") (pintype "passive"))
      (node (ref "ICSP1") (pin "6") (pinfunction "6_6") (pintype "passive"))
      (node (ref "IOH") (pin "7") (pinfunction "7_7") (pintype "passive"))
      (node (ref "L") (pin "C") (pinfunction "C_C") (pintype "passive"))
      (node (ref "ON") (pin "C") (pinfunction "C_C") (pintype "passive"))
      (node (ref "PC1") (pin "-") (pinfunction "-_-") (pintype "passive"))
      (node (ref "PC2") (pin "-") (pinfunction "-_-") (pintype "passive"))
      (node (ref "POWER") (pin "6") (pinfunction "6_6") (pintype "passive"))
      (node (ref "POWER") (pin "7") (pinfunction "7_7") (pintype "passive"))
      (node (ref "RESET") (pin "1") (pinfunction "1_1") (pintype "passive"))
      (node (ref "RESET") (pin "2") (pinfunction "2_2") (pintype "passive"))
      (node (ref "RN1") (pin "7") (pinfunction "2_7") (pintype "passive"))
      (node (ref "RN2") (pin "5") (pinfunction "2_5") (pintype "passive"))
      (node (ref "U1") (pin "1") (pinfunction "GND/ADJ_1") (pintype "input"))
      (node (ref "U2") (pin "2") (pinfunction "GND_2") (pintype "power_in"))
      (node (ref "U3") (pin "3") (pinfunction "GND_3") (pintype "power_in"))
      (node (ref "U3") (pin "33") (pinfunction "PAD_33") (pintype "power_in"))
      (node (ref "U5") (pin "4") (pinfunction "V-_4") (pintype "power_in"))
      (node (ref "X1") (pin "1") (pinfunction "1_1") (pintype "power_in"))
      (node (ref "X1") (pin "3") (pinfunction "3_3") (pintype "power_in"))
      (node (ref "Y2") (pin "2") (pinfunction "2_2") (pintype "passive"))
      (node (ref "ZU4") (pin "22") (pinfunction "AGND_22") (pintype "power_in"))
      (node (ref "ZU4") (pin "8") (pinfunction "GND_8") (pintype "power_in"))
    )
    (net (code "59") (name "Net-(RN2B-2)") (class "Default")
      (node (ref "RN2") (pin "7") (pinfunction "2_7") (pintype "passive"))
      (node (ref "RX") (pin "A") (pinfunction "A_A") (pintype "passive"))
      (node (ref "TP_RXL") (pin "X") (pinfunction "TESTP_X") (pintype "passive"))
    )
    (net (code "60") (name "Net-(RN2C-2)") (class "Default")
      (node (ref "RN2") (pin "6") (pinfunction "2_6") (pintype "passive"))
      (node (ref "TP_TXL") (pin "X") (pinfunction "TESTP_X") (pintype "passive"))
      (node (ref "TX") (pin "A") (pinfunction "A_A") (pintype "passive"))
    )
    (net (code "61") (name "Net-(RN4C-2)") (class "Default")
      (node (ref "ON") (pin "A") (pinfunction "A_A") (pintype "passive"))
      (node (ref "RN4") (pin "5") (pinfunction "2_5") (pintype "passive"))
      (node (ref "RN4") (pin "6") (pinfunction "2_6") (pintype "passive"))
      (node (ref "TP_ONL") (pin "X") (pinfunction "TESTP_X") (pintype "passive"))
    )
    (net (code "62") (name "Net-(TP_LL-TESTP)") (class "Default")
      (node (ref "L") (pin "A") (pinfunction "A_A") (pintype "passive"))
      (node (ref "RN2") (pin "1") (pinfunction "1_1") (pintype "passive"))
      (node (ref "TP_LL") (pin "X") (pinfunction "TESTP_X") (pintype "passive"))
    )
    (net (code "63") (name "unconnected-(ORIGIN-TESTP-PadX)") (class "Default")
      (node (ref "ORIGIN") (pin "X") (pinfunction "TESTP_X") (pintype "passive"))
    )
    (net (code "64") (name "unconnected-(POWER-Pad1)") (class "Default")
      (node (ref "POWER") (pin "1") (pinfunction "1_1") (pintype "passive"))
    )
    (net (code "65") (name "unconnected-(RN3B-1-Pad2)") (class "Default")
      (node (ref "RN3") (pin "2") (pinfunction "1_2") (pintype "passive"))
    )
    (net (code "66") (name "unconnected-(RN3B-2-Pad7)") (class "Default")
      (node (ref "RN3") (pin "7") (pinfunction "2_7") (pintype "passive"))
    )
    (net (code "67") (name "unconnected-(RN3C-1-Pad3)") (class "Default")
      (node (ref "RN3") (pin "3") (pinfunction "1_3") (pintype "passive"))
    )
    (net (code "68") (name "unconnected-(RN3C-2-Pad6)") (class "Default")
      (node (ref "RN3") (pin "6") (pinfunction "2_6") (pintype "passive"))
    )
    (net (code "69") (name "unconnected-(U2-NC{slash}FB-Pad4)") (class "Default")
      (node (ref "U2") (pin "4") (pinfunction "NC/FB_4") (pintype "passive"))
    )
    (net (code "70") (name "unconnected-(U3-(AIN0{slash}INT1)PD1-Pad7)") (class "Default")
      (node (ref "U3") (pin "7") (pinfunction "(AIN0/INT1)PD1_7") (pintype "bidirectional"))
    )
    (net (code "71") (name "unconnected-(U3-(AIN2{slash}PCINT11)PC2-Pad5)") (class "Default")
      (node (ref "U3") (pin "5") (pinfunction "(AIN2/PCINT11)PC2_5") (pintype "bidirectional"))
    )
    (net (code "72") (name "unconnected-(U3-(INT4{slash}ICP1{slash}CLK0)PC7-Pad22)") (class "Default")
      (node (ref "U3") (pin "22") (pinfunction "(INT4/ICP1/CLK0)PC7_22") (pintype "bidirectional"))
    )
    (net (code "73") (name "unconnected-(U3-(OC0B{slash}INT0)PD0-Pad6)") (class "Default")
      (node (ref "U3") (pin "6") (pinfunction "(OC0B/INT0)PD0_6") (pintype "bidirectional"))
    )
    (net (code "74") (name "unconnected-(U3-(OC1A{slash}PCINT8)PC6-Pad23)") (class "Default")
      (node (ref "U3") (pin "23") (pinfunction "(OC1A/PCINT8)PC6_23") (pintype "bidirectional"))
    )
    (net (code "75") (name "unconnected-(U3-(PCINT9{slash}OC1B)PC5-Pad25)") (class "Default")
      (node (ref "U3") (pin "25") (pinfunction "(PCINT9/OC1B)PC5_25") (pintype "bidirectional"))
    )
    (net (code "76") (name "unconnected-(U3-(PCINT10)PC4-Pad26)") (class "Default")
      (node (ref "U3") (pin "26") (pinfunction "(PCINT10)PC4_26") (pintype "bidirectional"))
    )
    (net (code "77") (name "unconnected-(U3-(RTS{slash}AIN5{slash}INT6)PD6-Pad12)") (class "Default")
      (node (ref "U3") (pin "12") (pinfunction "(RTS/AIN5/INT6)PD6_12") (pintype "bidirectional"))
    )
    (net (code "78") (name "unconnected-(U3-(SS{slash}PCINT0)PB0-Pad14)") (class "Default")
      (node (ref "U3") (pin "14") (pinfunction "(SS/PCINT0)PB0_14") (pintype "bidirectional"))
    )
  )
)
